# untitled.net
KiCad netlist of a schematic drawn in EAGLE
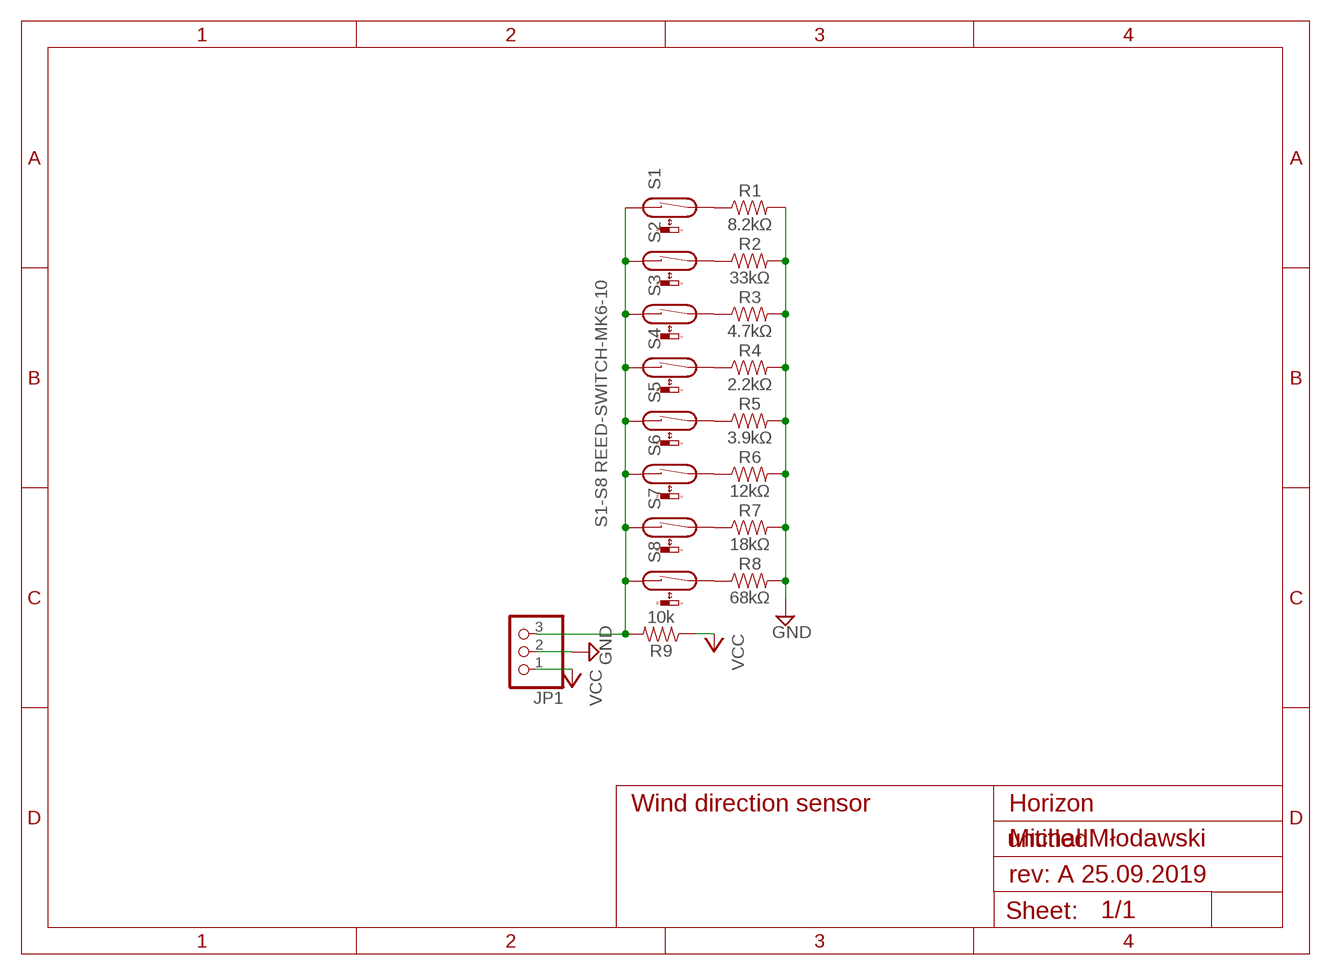
[diagram p0: schematic, sheet 1]

(export (version "E")
  (design (tool "Eeschema 10.0.6"))
  (components
    (comp (ref "JP1")
      (value "PINHD-1X3")
      (footprint "eagle-import:1X03")
      (libsource (lib "eagle-import") (part "PINHD-1X3"))
    )
    (comp (ref "R1")
      (value "8.2kΩ")
      (footprint "eagle-import:AXIAL-0.3")
      (libsource (lib "eagle-import") (part "1KOHM-HORIZ-1/4W-1%"))
    )
    (comp (ref "R2")
      (value "33kΩ")
      (footprint "eagle-import:AXIAL-0.3")
      (libsource (lib "eagle-import") (part "1KOHM-HORIZ-1/4W-1%"))
    )
    (comp (ref "R3")
      (value "4.7kΩ")
      (footprint "eagle-import:AXIAL-0.3")
      (libsource (lib "eagle-import") (part "1KOHM-HORIZ-1/4W-1%"))
    )
    (comp (ref "R4")
      (value "2.2kΩ")
      (footprint "eagle-import:AXIAL-0.3")
      (libsource (lib "eagle-import") (part "1KOHM-HORIZ-1/4W-1%"))
    )
    (comp (ref "R5")
      (value "3.9kΩ")
      (footprint "eagle-import:AXIAL-0.3")
      (libsource (lib "eagle-import") (part "1KOHM-HORIZ-1/4W-1%"))
    )
    (comp (ref "R6")
      (value "12kΩ")
      (footprint "eagle-import:AXIAL-0.3")
      (libsource (lib "eagle-import") (part "1KOHM-HORIZ-1/4W-1%"))
    )
    (comp (ref "R7")
      (value "18kΩ")
      (footprint "eagle-import:AXIAL-0.3")
      (libsource (lib "eagle-import") (part "1KOHM-HORIZ-1/4W-1%"))
    )
    (comp (ref "R8")
      (value "68kΩ")
      (footprint "eagle-import:AXIAL-0.3")
      (libsource (lib "eagle-import") (part "1KOHM-HORIZ-1/4W-1%"))
    )
    (comp (ref "R9")
      (value "10k")
      (footprint "eagle-import:AXIAL-0.3")
      (libsource (lib "eagle-import") (part "1KOHM-HORIZ-1/4W-1%"))
    )
    (comp (ref "S1")
      (value "REED-SWITCH-MK6-10")
      (footprint "eagle-import:MK6-10")
      (libsource (lib "eagle-import") (part "REED-SWITCH-MK6-10"))
    )
    (comp (ref "S2")
      (value "REED-SWITCH-MK6-10")
      (footprint "eagle-import:MK6-10")
      (libsource (lib "eagle-import") (part "REED-SWITCH-MK6-10"))
    )
    (comp (ref "S3")
      (value "REED-SWITCH-MK6-10")
      (footprint "eagle-import:MK6-10")
      (libsource (lib "eagle-import") (part "REED-SWITCH-MK6-10"))
    )
    (comp (ref "S4")
      (value "REED-SWITCH-MK6-10")
      (footprint "eagle-import:MK6-10")
      (libsource (lib "eagle-import") (part "REED-SWITCH-MK6-10"))
    )
    (comp (ref "S5")
      (value "REED-SWITCH-MK6-10")
      (footprint "eagle-import:MK6-10")
      (libsource (lib "eagle-import") (part "REED-SWITCH-MK6-10"))
    )
    (comp (ref "S6")
      (value "REED-SWITCH-MK6-10")
      (footprint "eagle-import:MK6-10")
      (libsource (lib "eagle-import") (part "REED-SWITCH-MK6-10"))
    )
    (comp (ref "S7")
      (value "REED-SWITCH-MK6-10")
      (footprint "eagle-import:MK6-10")
      (libsource (lib "eagle-import") (part "REED-SWITCH-MK6-10"))
    )
    (comp (ref "S8")
      (value "REED-SWITCH-MK6-10")
      (footprint "eagle-import:MK6-10")
      (libsource (lib "eagle-import") (part "REED-SWITCH-MK6-10"))
    )
  )
  (nets
    (net (code "1") (name "GND") (class "Default")
      (node (ref "JP1") (pin "2") (pinfunction "2_2") (pintype "passive"))
      (node (ref "R1") (pin "P$2") (pinfunction "2_P$2") (pintype "passive"))
      (node (ref "R2") (pin "P$2") (pinfunction "2_P$2") (pintype "passive"))
      (node (ref "R3") (pin "P$2") (pinfunction "2_P$2") (pintype "passive"))
      (node (ref "R4") (pin "P$2") (pinfunction "2_P$2") (pintype "passive"))
      (node (ref "R5") (pin "P$2") (pinfunction "2_P$2") (pintype "passive"))
      (node (ref "R6") (pin "P$2") (pinfunction "2_P$2") (pintype "passive"))
      (node (ref "R7") (pin "P$2") (pinfunction "2_P$2") (pintype "passive"))
      (node (ref "R8") (pin "P$2") (pinfunction "2_P$2") (pintype "passive"))
    )
    (net (code "2") (name "Net-(R1-1)") (class "Default")
      (node (ref "R1") (pin "P$1") (pinfunction "1_P$1") (pintype "passive"))
      (node (ref "S1") (pin "2") (pinfunction "2_2") (pintype "passive"))
    )
    (net (code "3") (name "Net-(R2-1)") (class "Default")
      (node (ref "R2") (pin "P$1") (pinfunction "1_P$1") (pintype "passive"))
      (node (ref "S2") (pin "2") (pinfunction "2_2") (pintype "passive"))
    )
    (net (code "4") (name "Net-(R3-1)") (class "Default")
      (node (ref "R3") (pin "P$1") (pinfunction "1_P$1") (pintype "passive"))
      (node (ref "S3") (pin "2") (pinfunction "2_2") (pintype "passive"))
    )
    (net (code "5") (name "Net-(R4-1)") (class "Default")
      (node (ref "R4") (pin "P$1") (pinfunction "1_P$1") (pintype "passive"))
      (node (ref "S4") (pin "2") (pinfunction "2_2") (pintype "passive"))
    )
    (net (code "6") (name "Net-(R5-1)") (class "Default")
      (node (ref "R5") (pin "P$1") (pinfunction "1_P$1") (pintype "passive"))
      (node (ref "S5") (pin "2") (pinfunction "2_2") (pintype "passive"))
    )
    (net (code "7") (name "Net-(R6-1)") (class "Default")
      (node (ref "R6") (pin "P$1") (pinfunction "1_P$1") (pintype "passive"))
      (node (ref "S6") (pin "2") (pinfunction "2_2") (pintype "passive"))
    )
    (net (code "8") (name "Net-(R7-1)") (class "Default")
      (node (ref "R7") (pin "P$1") (pinfunction "1_P$1") (pintype "passive"))
      (node (ref "S7") (pin "2") (pinfunction "2_2") (pintype "passive"))
    )
    (net (code "9") (name "Net-(R8-1)") (class "Default")
      (node (ref "R8") (pin "P$1") (pinfunction "1_P$1") (pintype "passive"))
      (node (ref "S8") (pin "2") (pinfunction "2_2") (pintype "passive"))
    )
    (net (code "10") (name "Net-(R9-2)") (class "Default")
      (node (ref "JP1") (pin "3") (pinfunction "3_3") (pintype "passive"))
      (node (ref "R9") (pin "P$2") (pinfunction "2_P$2") (pintype "passive"))
      (node (ref "S1") (pin "1") (pinfunction "1_1") (pintype "passive"))
      (node (ref "S2") (pin "1") (pinfunction "1_1") (pintype "passive"))
      (node (ref "S3") (pin "1") (pinfunction "1_1") (pintype "passive"))
      (node (ref "S4") (pin "1") (pinfunction "1_1") (pintype "passive"))
      (node (ref "S5") (pin "1") (pinfunction "1_1") (pintype "passive"))
      (node (ref "S6") (pin "1") (pinfunction "1_1") (pintype "passive"))
      (node (ref "S7") (pin "1") (pinfunction "1_1") (pintype "passive"))
      (node (ref "S8") (pin "1") (pinfunction "1_1") (pintype "passive"))
    )
    (net (code "11") (name "VCC") (class "Default")
      (node (ref "JP1") (pin "1") (pinfunction "1_1") (pintype "passive"))
      (node (ref "R9") (pin "P$1") (pinfunction "1_P$1") (pintype "passive"))
    )
  )
)
